# Power_Supply.net
KiCad netlist of a schematic drawn in Altium Designer
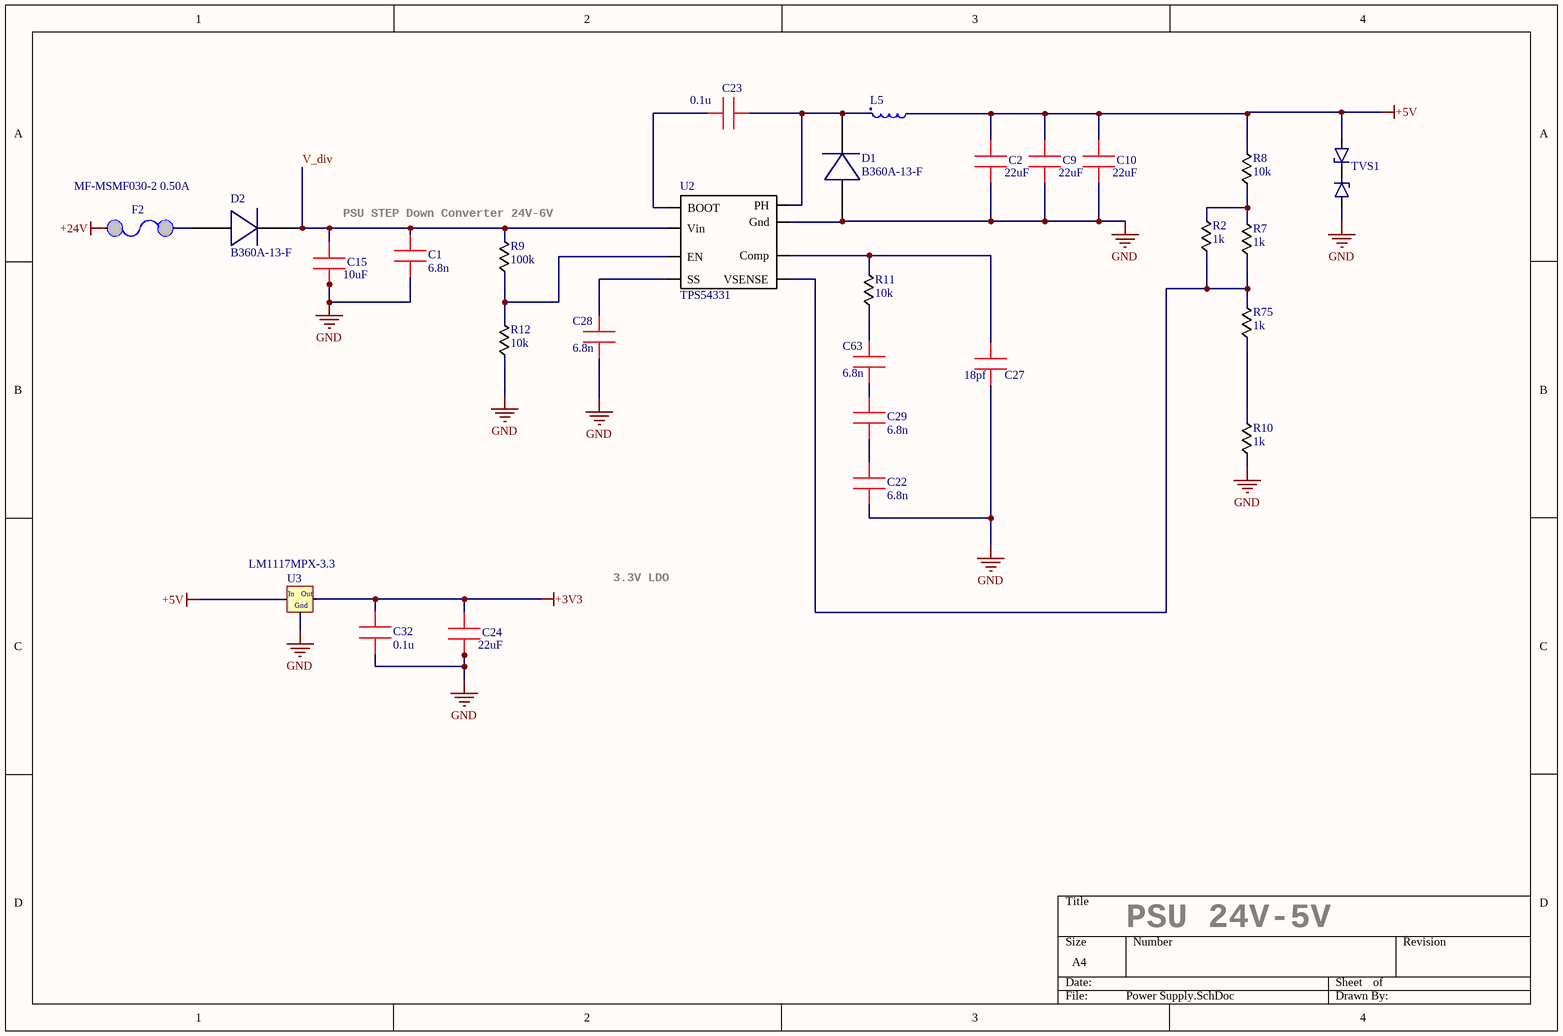
[diagram p0: Power Supply.SchDoc]

(export (version "E")
  (design (tool "Eeschema 10.0.6"))
  (components
    (comp (ref "C1")
      (value "6.8n")
      (footprint "0603 CAP")
      (description "CC0603KRX7R9BB682")
      (libsource (lib "kontr") (part "0603 CAP"))
    )
    (comp (ref "C2")
      (value "22uF")
      (footprint "CAP CER 1210 NP")
      (description "CC1210KKX5R7BB226")
      (libsource (lib "kontr") (part "0805 Cap"))
    )
    (comp (ref "C9")
      (value "22uF")
      (footprint "CAP CER 1210 NP")
      (description "CC1210KKX5R7BB226")
      (libsource (lib "kontr") (part "0805 Cap"))
    )
    (comp (ref "C10")
      (value "22uF")
      (footprint "CAP CER 1210 NP")
      (description "CC1210KKX5R7BB226")
      (libsource (lib "kontr") (part "0805 Cap"))
    )
    (comp (ref "C15")
      (value "10uF")
      (footprint "CAP CER 1210 NP")
      (description "GRM32ER71H106KA12L")
      (libsource (lib "kontr") (part "0805 Cap"))
    )
    (comp (ref "C22")
      (value "6.8n")
      (footprint "0603 CAP")
      (description "CC0603KRX7R9BB682")
      (libsource (lib "kontr") (part "0603 CAP"))
    )
    (comp (ref "C23")
      (value "0.1u")
      (footprint "0603 CAP")
      (description "GRM188R71E104KA01D")
      (libsource (lib "kontr") (part "0805 Cap"))
    )
    (comp (ref "C24")
      (value "22uF")
      (footprint "CAP CER 1210 NP")
      (description "CC1210KKX5R7BB226")
      (libsource (lib "kontr") (part "0805 Cap"))
    )
    (comp (ref "C27")
      (value "18pf")
      (footprint "0603 CAP")
      (description "GRM1885C1H180JA01D")
      (libsource (lib "kontr") (part "0805 Cap"))
    )
    (comp (ref "C28")
      (value "6.8n")
      (footprint "0603 CAP")
      (description "GRM188R71E104KA01D")
      (libsource (lib "kontr") (part "0805 Cap"))
    )
    (comp (ref "C29")
      (value "6.8n")
      (footprint "0603 CAP")
      (description "GRM188R71E104KA01D")
      (libsource (lib "kontr") (part "0805 Cap"))
    )
    (comp (ref "C32") (value "0.1u") (footprint "0603 CAP") (libsource (lib "kontr") (part "Capasitor 0805")))
    (comp (ref "C63")
      (value "6.8n")
      (footprint "0603 CAP")
      (description "GRM188R71E104KA01D")
      (libsource (lib "kontr") (part "0805 Cap"))
    )
    (comp (ref "D1")
      (value "B360A-13-F")
      (footprint "B340A-13-F")
      (libsource (lib "kontr") (part "B340A-13-F"))
    )
    (comp (ref "D2")
      (value "B360A-13-F")
      (footprint "B340A-13-F")
      (libsource (lib "kontr") (part "B340A-13-F"))
    )
    (comp (ref "F2")
      (value "MF-MSMF030-2 0.50A")
      (footprint "Fuse PTS")
      (libsource (lib "kontr") (part "Fuse PTS"))
    )
    (comp (ref "L5")
      (value "CDRH127/LDNP-220MC")
      (footprint "CDRH127/LDNP-270MC,")
      (libsource (lib "kontr") (part "CDRH127/LDNP-270MC"))
    )
    (comp (ref "R2")
      (value "1k")
      (footprint "0603 - RES")
      (description "RC0603FR-078K2")
      (libsource (lib "kontr") (part "Resistor 0805"))
    )
    (comp (ref "R7")
      (value "1k")
      (footprint "0603 - RES")
      (description "RC0603FR-078K2")
      (libsource (lib "kontr") (part "Resistor 0805"))
    )
    (comp (ref "R8")
      (value "10k")
      (footprint "0603 - RES")
      (description "RT0603FRE0710KL")
      (libsource (lib "kontr") (part "Resistor 0805"))
    )
    (comp (ref "R9")
      (value "100k")
      (footprint "0603 - RES")
      (description "RC0603FR-07100KL")
      (libsource (lib "kontr") (part "0603 RES"))
    )
    (comp (ref "R10")
      (value "1k")
      (footprint "0603 - RES")
      (description "RC0603FR-078K2")
      (libsource (lib "kontr") (part "Resistor 0805"))
    )
    (comp (ref "R11")
      (value "10k")
      (footprint "0603 - RES")
      (description "RT0603FRE0710KL")
      (libsource (lib "kontr") (part "Resistor 0805"))
    )
    (comp (ref "R12")
      (value "10k")
      (footprint "0603 - RES")
      (description "RT0603FRE0710KL")
      (libsource (lib "kontr") (part "Resistor 0805"))
    )
    (comp (ref "R75")
      (value "1k")
      (footprint "0603 - RES")
      (description "RC0603FR-078K2")
      (libsource (lib "kontr") (part "Resistor 0805"))
    )
    (comp (ref "TVS1")
      (value "TVS Diode")
      (footprint "SM6T")
      (description "SM6T12CA")
      (libsource (lib "kontr") (part "SM6T12CA"))
    )
    (comp (ref "U2") (value "TPS54331") (footprint "SOIC-8") (libsource (lib "kontr") (part "TPS54331")))
    (comp (ref "U3")
      (value "LM1117MPX-3.3")
      (footprint "SOT223")
      (libsource (lib "kontr") (part "NCV1117ST50T3G"))
    )
  )
  (nets
    (net (code "1") (name "+3V3") (class "Default")
      (node (ref "C24") (pin "2") (pinfunction "2_2") (pintype "passive"))
      (node (ref "C32") (pin "1") (pinfunction "1_1") (pintype "passive"))
      (node (ref "U3") (pin "2") (pinfunction "OUT_2") (pintype "passive"))
    )
    (net (code "2") (name "+5V") (class "Default")
      (node (ref "C10") (pin "2") (pinfunction "2_2") (pintype "passive"))
      (node (ref "C2") (pin "2") (pinfunction "2_2") (pintype "passive"))
      (node (ref "C9") (pin "2") (pinfunction "2_2") (pintype "passive"))
      (node (ref "L5") (pin "2") (pinfunction "2_2") (pintype "passive"))
      (node (ref "R8") (pin "2") (pintype "passive"))
      (node (ref "TVS1") (pin "2") (pinfunction "2_2") (pintype "passive"))
      (node (ref "U3") (pin "3") (pinfunction "IN_3") (pintype "passive"))
    )
    (net (code "3") (name "+24V") (class "Default")
      (node (ref "F2") (pin "2") (pinfunction "2_2") (pintype "passive"))
    )
    (net (code "4") (name "/V_div") (class "Default")
      (node (ref "C1") (pin "2") (pinfunction "2_2") (pintype "passive"))
      (node (ref "C15") (pin "2") (pinfunction "2_2") (pintype "passive"))
      (node (ref "D2") (pin "1") (pinfunction "1_1") (pintype "passive"))
      (node (ref "R9") (pin "2") (pintype "passive"))
      (node (ref "U2") (pin "2") (pinfunction "Vin_2") (pintype "passive"))
    )
    (net (code "5") (name "GND") (class "Default")
      (node (ref "C1") (pin "1") (pinfunction "1_1") (pintype "passive"))
      (node (ref "C10") (pin "1") (pinfunction "1_1") (pintype "passive"))
      (node (ref "C15") (pin "1") (pinfunction "1_1") (pintype "passive"))
      (node (ref "C2") (pin "1") (pinfunction "1_1") (pintype "passive"))
      (node (ref "C22") (pin "1") (pinfunction "1_1") (pintype "passive"))
      (node (ref "C24") (pin "1") (pinfunction "1_1") (pintype "passive"))
      (node (ref "C27") (pin "1") (pinfunction "1_1") (pintype "passive"))
      (node (ref "C28") (pin "1") (pinfunction "1_1") (pintype "passive"))
      (node (ref "C32") (pin "2") (pinfunction "2_2") (pintype "passive"))
      (node (ref "C9") (pin "1") (pinfunction "1_1") (pintype "passive"))
      (node (ref "D1") (pin "2") (pinfunction "1_2") (pintype "passive"))
      (node (ref "R10") (pin "1") (pintype "passive"))
      (node (ref "R12") (pin "1") (pintype "passive"))
      (node (ref "TVS1") (pin "1") (pinfunction "1_1") (pintype "passive"))
      (node (ref "U2") (pin "7") (pinfunction "Gnd_7") (pintype "passive"))
      (node (ref "U3") (pin "1") (pinfunction "GND_1") (pintype "passive"))
    )
    (net (code "6") (name "Net-(C22-Pad2)") (class "Default")
      (node (ref "C22") (pin "2") (pinfunction "2_2") (pintype "passive"))
      (node (ref "C29") (pin "1") (pinfunction "1_1") (pintype "passive"))
    )
    (net (code "7") (name "Net-(C29-Pad2)") (class "Default")
      (node (ref "C29") (pin "2") (pinfunction "2_2") (pintype "passive"))
      (node (ref "C63") (pin "1") (pinfunction "1_1") (pintype "passive"))
    )
    (net (code "8") (name "Net-(C63-Pad2)") (class "Default")
      (node (ref "C63") (pin "2") (pinfunction "2_2") (pintype "passive"))
      (node (ref "R11") (pin "1") (pintype "passive"))
    )
    (net (code "9") (name "Net-(D2-1-Pad2)") (class "Default")
      (node (ref "D2") (pin "2") (pinfunction "1_2") (pintype "passive"))
      (node (ref "F2") (pin "1") (pinfunction "1_1") (pintype "passive"))
    )
    (net (code "10") (name "Net-(R2-Pad2)") (class "Default")
      (node (ref "R2") (pin "2") (pintype "passive"))
      (node (ref "R7") (pin "2") (pintype "passive"))
      (node (ref "R8") (pin "1") (pintype "passive"))
    )
    (net (code "11") (name "Net-(R10-Pad2)") (class "Default")
      (node (ref "R10") (pin "2") (pintype "passive"))
      (node (ref "R75") (pin "1") (pintype "passive"))
    )
    (net (code "12") (name "Net-(U2-BOOT)") (class "Default")
      (node (ref "C23") (pin "1") (pinfunction "1_1") (pintype "passive"))
      (node (ref "U2") (pin "1") (pinfunction "BOOT_1") (pintype "passive"))
    )
    (net (code "13") (name "Net-(U2-Comp)") (class "Default")
      (node (ref "C27") (pin "2") (pinfunction "2_2") (pintype "passive"))
      (node (ref "R11") (pin "2") (pintype "passive"))
      (node (ref "U2") (pin "6") (pinfunction "Comp_6") (pintype "passive"))
    )
    (net (code "14") (name "Net-(U2-EN)") (class "Default")
      (node (ref "R12") (pin "2") (pintype "passive"))
      (node (ref "R9") (pin "1") (pintype "passive"))
      (node (ref "U2") (pin "3") (pinfunction "EN_3") (pintype "passive"))
    )
    (net (code "15") (name "Net-(U2-PH)") (class "Default")
      (node (ref "C23") (pin "2") (pinfunction "2_2") (pintype "passive"))
      (node (ref "D1") (pin "1") (pinfunction "1_1") (pintype "passive"))
      (node (ref "L5") (pin "1") (pinfunction "1_1") (pintype "passive"))
      (node (ref "U2") (pin "8") (pinfunction "PH_8") (pintype "passive"))
    )
    (net (code "16") (name "Net-(U2-SS)") (class "Default")
      (node (ref "C28") (pin "2") (pinfunction "2_2") (pintype "passive"))
      (node (ref "U2") (pin "4") (pinfunction "SS_4") (pintype "passive"))
    )
    (net (code "17") (name "Net-(U2-VSENSE)") (class "Default")
      (node (ref "R2") (pin "1") (pintype "passive"))
      (node (ref "R7") (pin "1") (pintype "passive"))
      (node (ref "R75") (pin "2") (pintype "passive"))
      (node (ref "U2") (pin "5") (pinfunction "VSENSE_5") (pintype "passive"))
    )
  )
)
